# LED_Scematic_Version3.net
KiCad netlist of a schematic drawn in EAGLE
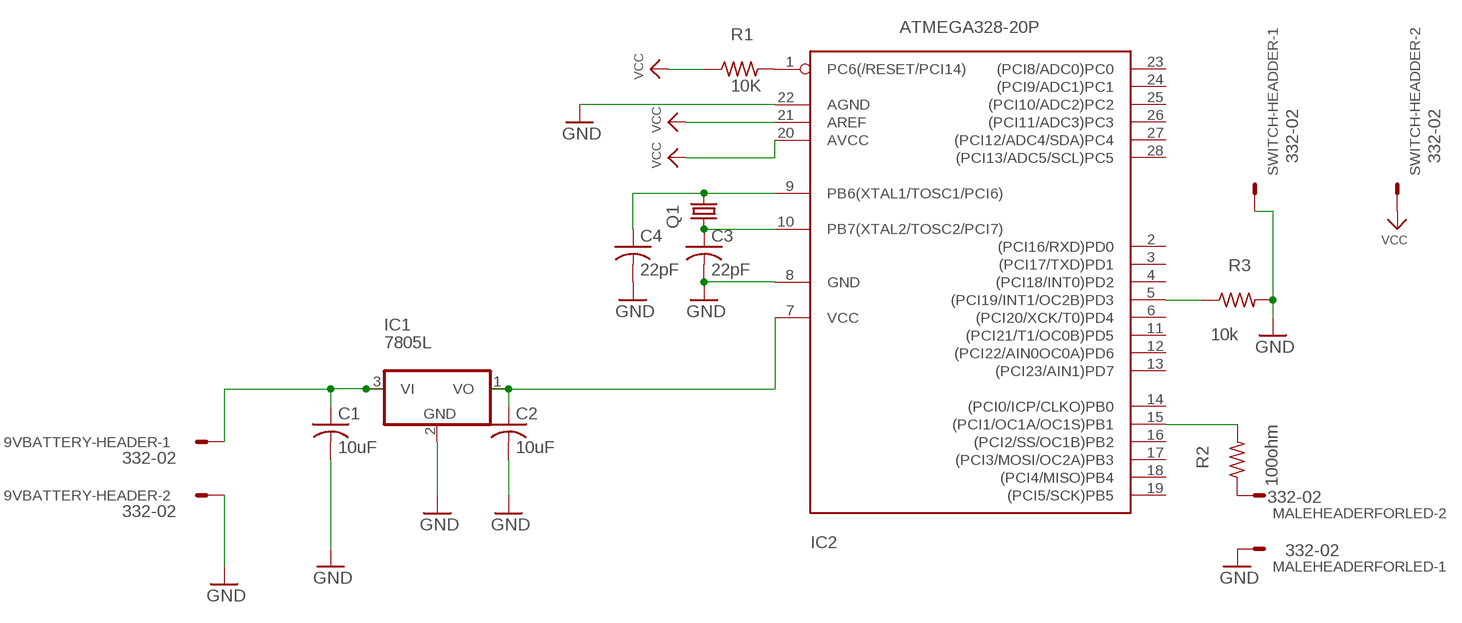
[diagram p0: schematic, sheet 1]

(export (version "E")
  (design (tool "Eeschema 10.0.6"))
  (components
    (comp (ref "9VBATTERY-HEADER")
      (value "332-02")
      (footprint "eagle-import:332-02")
      (libsource (lib "eagle-import") (part "332-02"))
    )
    (comp (ref "C1")
      (value "10uF")
      (footprint "eagle-import:C025-040X050")
      (libsource (lib "eagle-import") (part "C-US025-040X050"))
    )
    (comp (ref "C2")
      (value "10uF")
      (footprint "eagle-import:C025-040X050")
      (libsource (lib "eagle-import") (part "C-US025-040X050"))
    )
    (comp (ref "C3")
      (value "22pF")
      (footprint "eagle-import:C025-040X050")
      (libsource (lib "eagle-import") (part "C-US025-040X050"))
    )
    (comp (ref "C4")
      (value "22pF")
      (footprint "eagle-import:C025-040X050")
      (libsource (lib "eagle-import") (part "C-US025-040X050"))
    )
    (comp (ref "IC1")
      (value "7805L")
      (footprint "eagle-import:TO92")
      (libsource (lib "eagle-import") (part "78L05"))
    )
    (comp (ref "IC2")
      (value "ATMEGA328-20P")
      (footprint "eagle-import:DIL28-3")
      (libsource (lib "eagle-import") (part "ATMEGA328P-20"))
    )
    (comp (ref "MALEHEADERFORLED")
      (value "332-02")
      (footprint "eagle-import:332-02")
      (libsource (lib "eagle-import") (part "332-02"))
    )
    (comp (ref "Q1")
      (value "CRYSTALHC49S")
      (footprint "eagle-import:HC49_S")
      (libsource (lib "eagle-import") (part "CRYSTALHC49S"))
    )
    (comp (ref "R1")
      (value "10K")
      (footprint "eagle-import:0207_12")
      (libsource (lib "eagle-import") (part "R-US_0207/12"))
    )
    (comp (ref "R2")
      (value "100ohm")
      (footprint "eagle-import:0207_12")
      (libsource (lib "eagle-import") (part "R-US_0207/12"))
    )
    (comp (ref "R3")
      (value "10k")
      (footprint "eagle-import:0207_12")
      (fields (field (name "SPICEPREFIX") "R"))
      (libsource (lib "eagle-import") (part "R-US_0207/12"))
    )
    (comp (ref "SWITCH-HEADDER")
      (value "332-02")
      (footprint "eagle-import:332-02")
      (libsource (lib "eagle-import") (part "332-02"))
    )
  )
  (nets
    (net (code "1") (name "GND") (class "Default")
      (node (ref "9VBATTERY-HEADER") (pin "2") (pinfunction "S_2") (pintype "passive"))
      (node (ref "C1") (pin "2") (pinfunction "2_2") (pintype "passive"))
      (node (ref "C2") (pin "2") (pinfunction "2_2") (pintype "passive"))
      (node (ref "C3") (pin "2") (pinfunction "2_2") (pintype "passive"))
      (node (ref "C4") (pin "2") (pinfunction "2_2") (pintype "passive"))
      (node (ref "IC1") (pin "2") (pinfunction "GND_2") (pintype "passive"))
      (node (ref "IC2") (pin "22") (pinfunction "AGND_22") (pintype "bidirectional"))
      (node (ref "IC2") (pin "8") (pinfunction "GND_8") (pintype "bidirectional"))
      (node (ref "MALEHEADERFORLED") (pin "1") (pinfunction "S_1") (pintype "passive"))
      (node (ref "R3") (pin "2") (pinfunction "2_2") (pintype "passive"))
      (node (ref "SWITCH-HEADDER") (pin "1") (pinfunction "S_1") (pintype "passive"))
    )
    (net (code "2") (name "Net-(9VBATTERY-HEADERA-S)") (class "Default")
      (node (ref "9VBATTERY-HEADER") (pin "1") (pinfunction "S_1") (pintype "passive"))
      (node (ref "C1") (pin "1") (pinfunction "1_1") (pintype "passive"))
      (node (ref "IC1") (pin "3") (pinfunction "VI_3") (pintype "input"))
    )
    (net (code "3") (name "Net-(IC1-VO)") (class "Default")
      (node (ref "C2") (pin "1") (pinfunction "1_1") (pintype "passive"))
      (node (ref "IC1") (pin "1") (pinfunction "VO_1") (pintype "passive"))
      (node (ref "IC2") (pin "7") (pinfunction "VCC_7") (pintype "bidirectional"))
    )
    (net (code "4") (name "Net-(IC2-(PCI1{slash}OC1A{slash}OC1S)PB1)") (class "Default")
      (node (ref "IC2") (pin "15") (pinfunction "(PCI1/OC1A/OC1S)PB1_15") (pintype "bidirectional"))
      (node (ref "R2") (pin "2") (pinfunction "2_2") (pintype "passive"))
    )
    (net (code "5") (name "Net-(IC2-(PCI19{slash}INT1{slash}OC2B)PD3)") (class "Default")
      (node (ref "IC2") (pin "5") (pinfunction "(PCI19/INT1/OC2B)PD3_5") (pintype "bidirectional"))
      (node (ref "R3") (pin "1") (pinfunction "1_1") (pintype "passive"))
    )
    (net (code "6") (name "Net-(IC2-PB6(XTAL1{slash}TOSC1{slash}PCI6))") (class "Default")
      (node (ref "C4") (pin "1") (pinfunction "1_1") (pintype "passive"))
      (node (ref "IC2") (pin "9") (pinfunction "PB6(XTAL1/TOSC1/PCI6)_9") (pintype "bidirectional"))
      (node (ref "Q1") (pin "2") (pinfunction "2_2") (pintype "passive"))
    )
    (net (code "7") (name "Net-(IC2-PB7(XTAL2{slash}TOSC2{slash}PCI7))") (class "Default")
      (node (ref "C3") (pin "1") (pinfunction "1_1") (pintype "passive"))
      (node (ref "IC2") (pin "10") (pinfunction "PB7(XTAL2/TOSC2/PCI7)_10") (pintype "bidirectional"))
      (node (ref "Q1") (pin "1") (pinfunction "1_1") (pintype "passive"))
    )
    (net (code "8") (name "Net-(IC2-PC6({slash}RESET{slash}PCI14))") (class "Default")
      (node (ref "IC2") (pin "1") (pinfunction "PC6(/RESET/PCI14)_1") (pintype "bidirectional"))
      (node (ref "R1") (pin "2") (pinfunction "2_2") (pintype "passive"))
    )
    (net (code "9") (name "Net-(MALEHEADERFORLEDB-S)") (class "Default")
      (node (ref "MALEHEADERFORLED") (pin "2") (pinfunction "S_2") (pintype "passive"))
      (node (ref "R2") (pin "1") (pinfunction "1_1") (pintype "passive"))
    )
    (net (code "10") (name "VCC") (class "Default")
      (node (ref "IC2") (pin "20") (pinfunction "AVCC_20") (pintype "bidirectional"))
      (node (ref "IC2") (pin "21") (pinfunction "AREF_21") (pintype "bidirectional"))
      (node (ref "R1") (pin "1") (pinfunction "1_1") (pintype "passive"))
      (node (ref "SWITCH-HEADDER") (pin "2") (pinfunction "S_2") (pintype "passive"))
    )
    (net (code "11") (name "unconnected-(IC2-(PCI0{slash}ICP{slash}CLKO)PB0-Pad14)") (class "Default")
      (node (ref "IC2") (pin "14") (pinfunction "(PCI0/ICP/CLKO)PB0_14") (pintype "bidirectional"))
    )
    (net (code "12") (name "unconnected-(IC2-(PCI2{slash}SS{slash}OC1B)PB2-Pad16)") (class "Default")
      (node (ref "IC2") (pin "16") (pinfunction "(PCI2/SS/OC1B)PB2_16") (pintype "bidirectional"))
    )
    (net (code "13") (name "unconnected-(IC2-(PCI3{slash}MOSI{slash}OC2A)PB3-Pad17)") (class "Default")
      (node (ref "IC2") (pin "17") (pinfunction "(PCI3/MOSI/OC2A)PB3_17") (pintype "bidirectional"))
    )
    (net (code "14") (name "unconnected-(IC2-(PCI4{slash}MISO)PB4-Pad18)") (class "Default")
      (node (ref "IC2") (pin "18") (pinfunction "(PCI4/MISO)PB4_18") (pintype "bidirectional"))
    )
    (net (code "15") (name "unconnected-(IC2-(PCI5{slash}SCK)PB5-Pad19)") (class "Default")
      (node (ref "IC2") (pin "19") (pinfunction "(PCI5/SCK)PB5_19") (pintype "bidirectional"))
    )
    (net (code "16") (name "unconnected-(IC2-(PCI8{slash}ADC0)PC0-Pad23)") (class "Default")
      (node (ref "IC2") (pin "23") (pinfunction "(PCI8/ADC0)PC0_23") (pintype "bidirectional"))
    )
    (net (code "17") (name "unconnected-(IC2-(PCI9{slash}ADC1)PC1-Pad24)") (class "Default")
      (node (ref "IC2") (pin "24") (pinfunction "(PCI9/ADC1)PC1_24") (pintype "bidirectional"))
    )
    (net (code "18") (name "unconnected-(IC2-(PCI10{slash}ADC2)PC2-Pad25)") (class "Default")
      (node (ref "IC2") (pin "25") (pinfunction "(PCI10/ADC2)PC2_25") (pintype "bidirectional"))
    )
    (net (code "19") (name "unconnected-(IC2-(PCI11{slash}ADC3)PC3-Pad26)") (class "Default")
      (node (ref "IC2") (pin "26") (pinfunction "(PCI11/ADC3)PC3_26") (pintype "bidirectional"))
    )
    (net (code "20") (name "unconnected-(IC2-(PCI12{slash}ADC4{slash}SDA)PC4-Pad27)") (class "Default")
      (node (ref "IC2") (pin "27") (pinfunction "(PCI12/ADC4/SDA)PC4_27") (pintype "bidirectional"))
    )
    (net (code "21") (name "unconnected-(IC2-(PCI13{slash}ADC5{slash}SCL)PC5-Pad28)") (class "Default")
      (node (ref "IC2") (pin "28") (pinfunction "(PCI13/ADC5/SCL)PC5_28") (pintype "bidirectional"))
    )
    (net (code "22") (name "unconnected-(IC2-(PCI16{slash}RXD)PD0-Pad2)") (class "Default")
      (node (ref "IC2") (pin "2") (pinfunction "(PCI16/RXD)PD0_2") (pintype "bidirectional"))
    )
    (net (code "23") (name "unconnected-(IC2-(PCI17{slash}TXD)PD1-Pad3)") (class "Default")
      (node (ref "IC2") (pin "3") (pinfunction "(PCI17/TXD)PD1_3") (pintype "bidirectional"))
    )
    (net (code "24") (name "unconnected-(IC2-(PCI18{slash}INT0)PD2-Pad4)") (class "Default")
      (node (ref "IC2") (pin "4") (pinfunction "(PCI18/INT0)PD2_4") (pintype "bidirectional"))
    )
    (net (code "25") (name "unconnected-(IC2-(PCI20{slash}XCK{slash}T0)PD4-Pad6)") (class "Default")
      (node (ref "IC2") (pin "6") (pinfunction "(PCI20/XCK/T0)PD4_6") (pintype "bidirectional"))
    )
    (net (code "26") (name "unconnected-(IC2-(PCI21{slash}T1{slash}OC0B)PD5-Pad11)") (class "Default")
      (node (ref "IC2") (pin "11") (pinfunction "(PCI21/T1/OC0B)PD5_11") (pintype "bidirectional"))
    )
    (net (code "27") (name "unconnected-(IC2-(PCI22{slash}AIN0OC0A)PD6-Pad12)") (class "Default")
      (node (ref "IC2") (pin "12") (pinfunction "(PCI22/AIN0OC0A)PD6_12") (pintype "bidirectional"))
    )
    (net (code "28") (name "unconnected-(IC2-(PCI23{slash}AIN1)PD7-Pad13)") (class "Default")
      (node (ref "IC2") (pin "13") (pinfunction "(PCI23/AIN1)PD7_13") (pintype "bidirectional"))
    )
  )
)
